# 4-layer-microstrip-nomask-osh-v2.net
KiCad netlist of a schematic drawn in EAGLE
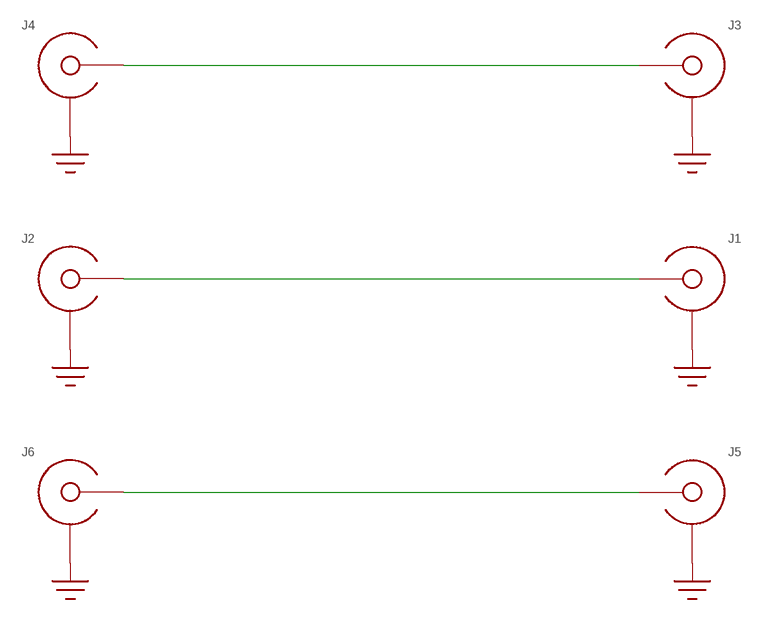
[diagram p0: schematic, sheet 1]

(export (version "E")
  (design (tool "Eeschema 10.0.6"))
  (components
    (comp (ref "J1")
      (value "SMA-EDGE-LAUNCH4L-4020-TAPER-FIXED")
      (footprint "eagle-import:SMA_EDGE_LAUNCH_4L_4020_TAPER_FIXED")
      (libsource (lib "eagle-import") (part "SMA-EDGE-LAUNCH4L-4020-TAPER-FIXED"))
    )
    (comp (ref "J2")
      (value "SMA-EDGE-LAUNCH4L-4020-TAPER-FIXED")
      (footprint "eagle-import:SMA_EDGE_LAUNCH_4L_4020_TAPER_FIXED")
      (libsource (lib "eagle-import") (part "SMA-EDGE-LAUNCH4L-4020-TAPER-FIXED"))
    )
    (comp (ref "J3")
      (value "SMA-EDGE-LAUNCH4L-4020-TAPER-FIXED")
      (footprint "eagle-import:SMA_EDGE_LAUNCH_4L_4020_TAPER_FIXED")
      (libsource (lib "eagle-import") (part "SMA-EDGE-LAUNCH4L-4020-TAPER-FIXED"))
    )
    (comp (ref "J4")
      (value "SMA-EDGE-LAUNCH4L-4020-TAPER-FIXED")
      (footprint "eagle-import:SMA_EDGE_LAUNCH_4L_4020_TAPER_FIXED")
      (libsource (lib "eagle-import") (part "SMA-EDGE-LAUNCH4L-4020-TAPER-FIXED"))
    )
    (comp (ref "J5")
      (value "SMA-EDGE-LAUNCH4L-4020-TAPER-FIXED")
      (footprint "eagle-import:SMA_EDGE_LAUNCH_4L_4020_TAPER_FIXED")
      (libsource (lib "eagle-import") (part "SMA-EDGE-LAUNCH4L-4020-TAPER-FIXED"))
    )
    (comp (ref "J6")
      (value "SMA-EDGE-LAUNCH4L-4020-TAPER-FIXED")
      (footprint "eagle-import:SMA_EDGE_LAUNCH_4L_4020_TAPER_FIXED")
      (libsource (lib "eagle-import") (part "SMA-EDGE-LAUNCH4L-4020-TAPER-FIXED"))
    )
  )
  (nets
    (net (code "1") (name "GND") (class "Default")
      (node (ref "J1") (pin "BOTTOM_GND") (pinfunction "SHIELD_BOTTOM_GND") (pintype "bidirectional"))
      (node (ref "J1") (pin "GND@1") (pinfunction "SHIELD_GND@1") (pintype "bidirectional"))
      (node (ref "J1") (pin "GND@14") (pinfunction "SHIELD_GND@14") (pintype "bidirectional"))
      (node (ref "J1") (pin "GND@15") (pinfunction "SHIELD_GND@15") (pintype "bidirectional"))
      (node (ref "J1") (pin "GND@16") (pinfunction "SHIELD_GND@16") (pintype "bidirectional"))
      (node (ref "J1") (pin "GND@17") (pinfunction "SHIELD_GND@17") (pintype "bidirectional"))
      (node (ref "J1") (pin "GND@2") (pinfunction "SHIELD_GND@2") (pintype "bidirectional"))
      (node (ref "J1") (pin "GND@3") (pinfunction "SHIELD_GND@3") (pintype "bidirectional"))
      (node (ref "J1") (pin "GND@4") (pinfunction "SHIELD_GND@4") (pintype "bidirectional"))
      (node (ref "J1") (pin "GND@5") (pinfunction "SHIELD_GND@5") (pintype "bidirectional"))
      (node (ref "J1") (pin "GND@6") (pinfunction "SHIELD_GND@6") (pintype "bidirectional"))
      (node (ref "J1") (pin "GND@7") (pinfunction "SHIELD_GND@7") (pintype "bidirectional"))
      (node (ref "J1") (pin "GND@8") (pinfunction "SHIELD_GND@8") (pintype "bidirectional"))
      (node (ref "J1") (pin "GND_PAD1") (pinfunction "SHIELD_GND_PAD1") (pintype "bidirectional"))
      (node (ref "J1") (pin "GND_PAD2") (pinfunction "SHIELD_GND_PAD2") (pintype "bidirectional"))
      (node (ref "J1") (pin "P$1") (pinfunction "SHIELD_P$1") (pintype "bidirectional"))
      (node (ref "J1") (pin "P$2") (pinfunction "SHIELD_P$2") (pintype "bidirectional"))
      (node (ref "J2") (pin "BOTTOM_GND") (pinfunction "SHIELD_BOTTOM_GND") (pintype "bidirectional"))
      (node (ref "J2") (pin "GND@1") (pinfunction "SHIELD_GND@1") (pintype "bidirectional"))
      (node (ref "J2") (pin "GND@14") (pinfunction "SHIELD_GND@14") (pintype "bidirectional"))
      (node (ref "J2") (pin "GND@15") (pinfunction "SHIELD_GND@15") (pintype "bidirectional"))
      (node (ref "J2") (pin "GND@16") (pinfunction "SHIELD_GND@16") (pintype "bidirectional"))
      (node (ref "J2") (pin "GND@17") (pinfunction "SHIELD_GND@17") (pintype "bidirectional"))
      (node (ref "J2") (pin "GND@2") (pinfunction "SHIELD_GND@2") (pintype "bidirectional"))
      (node (ref "J2") (pin "GND@3") (pinfunction "SHIELD_GND@3") (pintype "bidirectional"))
      (node (ref "J2") (pin "GND@4") (pinfunction "SHIELD_GND@4") (pintype "bidirectional"))
      (node (ref "J2") (pin "GND@5") (pinfunction "SHIELD_GND@5") (pintype "bidirectional"))
      (node (ref "J2") (pin "GND@6") (pinfunction "SHIELD_GND@6") (pintype "bidirectional"))
      (node (ref "J2") (pin "GND@7") (pinfunction "SHIELD_GND@7") (pintype "bidirectional"))
      (node (ref "J2") (pin "GND@8") (pinfunction "SHIELD_GND@8") (pintype "bidirectional"))
      (node (ref "J2") (pin "GND_PAD1") (pinfunction "SHIELD_GND_PAD1") (pintype "bidirectional"))
      (node (ref "J2") (pin "GND_PAD2") (pinfunction "SHIELD_GND_PAD2") (pintype "bidirectional"))
      (node (ref "J2") (pin "P$1") (pinfunction "SHIELD_P$1") (pintype "bidirectional"))
      (node (ref "J2") (pin "P$2") (pinfunction "SHIELD_P$2") (pintype "bidirectional"))
      (node (ref "J3") (pin "BOTTOM_GND") (pinfunction "SHIELD_BOTTOM_GND") (pintype "bidirectional"))
      (node (ref "J3") (pin "GND@1") (pinfunction "SHIELD_GND@1") (pintype "bidirectional"))
      (node (ref "J3") (pin "GND@14") (pinfunction "SHIELD_GND@14") (pintype "bidirectional"))
      (node (ref "J3") (pin "GND@15") (pinfunction "SHIELD_GND@15") (pintype "bidirectional"))
      (node (ref "J3") (pin "GND@16") (pinfunction "SHIELD_GND@16") (pintype "bidirectional"))
      (node (ref "J3") (pin "GND@17") (pinfunction "SHIELD_GND@17") (pintype "bidirectional"))
      (node (ref "J3") (pin "GND@2") (pinfunction "SHIELD_GND@2") (pintype "bidirectional"))
      (node (ref "J3") (pin "GND@3") (pinfunction "SHIELD_GND@3") (pintype "bidirectional"))
      (node (ref "J3") (pin "GND@4") (pinfunction "SHIELD_GND@4") (pintype "bidirectional"))
      (node (ref "J3") (pin "GND@5") (pinfunction "SHIELD_GND@5") (pintype "bidirectional"))
      (node (ref "J3") (pin "GND@6") (pinfunction "SHIELD_GND@6") (pintype "bidirectional"))
      (node (ref "J3") (pin "GND@7") (pinfunction "SHIELD_GND@7") (pintype "bidirectional"))
      (node (ref "J3") (pin "GND@8") (pinfunction "SHIELD_GND@8") (pintype "bidirectional"))
      (node (ref "J3") (pin "GND_PAD1") (pinfunction "SHIELD_GND_PAD1") (pintype "bidirectional"))
      (node (ref "J3") (pin "GND_PAD2") (pinfunction "SHIELD_GND_PAD2") (pintype "bidirectional"))
      (node (ref "J3") (pin "P$1") (pinfunction "SHIELD_P$1") (pintype "bidirectional"))
      (node (ref "J3") (pin "P$2") (pinfunction "SHIELD_P$2") (pintype "bidirectional"))
      (node (ref "J4") (pin "BOTTOM_GND") (pinfunction "SHIELD_BOTTOM_GND") (pintype "bidirectional"))
      (node (ref "J4") (pin "GND@1") (pinfunction "SHIELD_GND@1") (pintype "bidirectional"))
      (node (ref "J4") (pin "GND@14") (pinfunction "SHIELD_GND@14") (pintype "bidirectional"))
      (node (ref "J4") (pin "GND@15") (pinfunction "SHIELD_GND@15") (pintype "bidirectional"))
      (node (ref "J4") (pin "GND@16") (pinfunction "SHIELD_GND@16") (pintype "bidirectional"))
      (node (ref "J4") (pin "GND@17") (pinfunction "SHIELD_GND@17") (pintype "bidirectional"))
      (node (ref "J4") (pin "GND@2") (pinfunction "SHIELD_GND@2") (pintype "bidirectional"))
      (node (ref "J4") (pin "GND@3") (pinfunction "SHIELD_GND@3") (pintype "bidirectional"))
      (node (ref "J4") (pin "GND@4") (pinfunction "SHIELD_GND@4") (pintype "bidirectional"))
      (node (ref "J4") (pin "GND@5") (pinfunction "SHIELD_GND@5") (pintype "bidirectional"))
      (node (ref "J4") (pin "GND@6") (pinfunction "SHIELD_GND@6") (pintype "bidirectional"))
      (node (ref "J4") (pin "GND@7") (pinfunction "SHIELD_GND@7") (pintype "bidirectional"))
      (node (ref "J4") (pin "GND@8") (pinfunction "SHIELD_GND@8") (pintype "bidirectional"))
      (node (ref "J4") (pin "GND_PAD1") (pinfunction "SHIELD_GND_PAD1") (pintype "bidirectional"))
      (node (ref "J4") (pin "GND_PAD2") (pinfunction "SHIELD_GND_PAD2") (pintype "bidirectional"))
      (node (ref "J4") (pin "P$1") (pinfunction "SHIELD_P$1") (pintype "bidirectional"))
      (node (ref "J4") (pin "P$2") (pinfunction "SHIELD_P$2") (pintype "bidirectional"))
      (node (ref "J5") (pin "BOTTOM_GND") (pinfunction "SHIELD_BOTTOM_GND") (pintype "bidirectional"))
      (node (ref "J5") (pin "GND@1") (pinfunction "SHIELD_GND@1") (pintype "bidirectional"))
      (node (ref "J5") (pin "GND@14") (pinfunction "SHIELD_GND@14") (pintype "bidirectional"))
      (node (ref "J5") (pin "GND@15") (pinfunction "SHIELD_GND@15") (pintype "bidirectional"))
      (node (ref "J5") (pin "GND@16") (pinfunction "SHIELD_GND@16") (pintype "bidirectional"))
      (node (ref "J5") (pin "GND@17") (pinfunction "SHIELD_GND@17") (pintype "bidirectional"))
      (node (ref "J5") (pin "GND@2") (pinfunction "SHIELD_GND@2") (pintype "bidirectional"))
      (node (ref "J5") (pin "GND@3") (pinfunction "SHIELD_GND@3") (pintype "bidirectional"))
      (node (ref "J5") (pin "GND@4") (pinfunction "SHIELD_GND@4") (pintype "bidirectional"))
      (node (ref "J5") (pin "GND@5") (pinfunction "SHIELD_GND@5") (pintype "bidirectional"))
      (node (ref "J5") (pin "GND@6") (pinfunction "SHIELD_GND@6") (pintype "bidirectional"))
      (node (ref "J5") (pin "GND@7") (pinfunction "SHIELD_GND@7") (pintype "bidirectional"))
      (node (ref "J5") (pin "GND@8") (pinfunction "SHIELD_GND@8") (pintype "bidirectional"))
      (node (ref "J5") (pin "GND_PAD1") (pinfunction "SHIELD_GND_PAD1") (pintype "bidirectional"))
      (node (ref "J5") (pin "GND_PAD2") (pinfunction "SHIELD_GND_PAD2") (pintype "bidirectional"))
      (node (ref "J5") (pin "P$1") (pinfunction "SHIELD_P$1") (pintype "bidirectional"))
      (node (ref "J5") (pin "P$2") (pinfunction "SHIELD_P$2") (pintype "bidirectional"))
      (node (ref "J6") (pin "BOTTOM_GND") (pinfunction "SHIELD_BOTTOM_GND") (pintype "bidirectional"))
      (node (ref "J6") (pin "GND@1") (pinfunction "SHIELD_GND@1") (pintype "bidirectional"))
      (node (ref "J6") (pin "GND@14") (pinfunction "SHIELD_GND@14") (pintype "bidirectional"))
      (node (ref "J6") (pin "GND@15") (pinfunction "SHIELD_GND@15") (pintype "bidirectional"))
      (node (ref "J6") (pin "GND@16") (pinfunction "SHIELD_GND@16") (pintype "bidirectional"))
      (node (ref "J6") (pin "GND@17") (pinfunction "SHIELD_GND@17") (pintype "bidirectional"))
      (node (ref "J6") (pin "GND@2") (pinfunction "SHIELD_GND@2") (pintype "bidirectional"))
      (node (ref "J6") (pin "GND@3") (pinfunction "SHIELD_GND@3") (pintype "bidirectional"))
      (node (ref "J6") (pin "GND@4") (pinfunction "SHIELD_GND@4") (pintype "bidirectional"))
      (node (ref "J6") (pin "GND@5") (pinfunction "SHIELD_GND@5") (pintype "bidirectional"))
      (node (ref "J6") (pin "GND@6") (pinfunction "SHIELD_GND@6") (pintype "bidirectional"))
      (node (ref "J6") (pin "GND@7") (pinfunction "SHIELD_GND@7") (pintype "bidirectional"))
      (node (ref "J6") (pin "GND@8") (pinfunction "SHIELD_GND@8") (pintype "bidirectional"))
      (node (ref "J6") (pin "GND_PAD1") (pinfunction "SHIELD_GND_PAD1") (pintype "bidirectional"))
      (node (ref "J6") (pin "GND_PAD2") (pinfunction "SHIELD_GND_PAD2") (pintype "bidirectional"))
      (node (ref "J6") (pin "P$1") (pinfunction "SHIELD_P$1") (pintype "bidirectional"))
      (node (ref "J6") (pin "P$2") (pinfunction "SHIELD_P$2") (pintype "bidirectional"))
    )
    (net (code "2") (name "Net-(J1-CENTER-PadCENTER@1)") (class "Default")
      (node (ref "J1") (pin "CENTER@1") (pinfunction "CENTER_CENTER@1") (pintype "bidirectional"))
      (node (ref "J1") (pin "P$3") (pinfunction "CENTER_P$3") (pintype "bidirectional"))
      (node (ref "J2") (pin "CENTER@1") (pinfunction "CENTER_CENTER@1") (pintype "bidirectional"))
      (node (ref "J2") (pin "P$3") (pinfunction "CENTER_P$3") (pintype "bidirectional"))
    )
    (net (code "3") (name "Net-(J3-CENTER-PadCENTER@1)") (class "Default")
      (node (ref "J3") (pin "CENTER@1") (pinfunction "CENTER_CENTER@1") (pintype "bidirectional"))
      (node (ref "J3") (pin "P$3") (pinfunction "CENTER_P$3") (pintype "bidirectional"))
      (node (ref "J4") (pin "CENTER@1") (pinfunction "CENTER_CENTER@1") (pintype "bidirectional"))
      (node (ref "J4") (pin "P$3") (pinfunction "CENTER_P$3") (pintype "bidirectional"))
    )
    (net (code "4") (name "Net-(J5-CENTER-PadCENTER@1)") (class "Default")
      (node (ref "J5") (pin "CENTER@1") (pinfunction "CENTER_CENTER@1") (pintype "bidirectional"))
      (node (ref "J5") (pin "P$3") (pinfunction "CENTER_P$3") (pintype "bidirectional"))
      (node (ref "J6") (pin "CENTER@1") (pinfunction "CENTER_CENTER@1") (pintype "bidirectional"))
      (node (ref "J6") (pin "P$3") (pinfunction "CENTER_P$3") (pintype "bidirectional"))
    )
  )
)
